# p2m-001.net
KiCad netlist of a schematic drawn in EAGLE
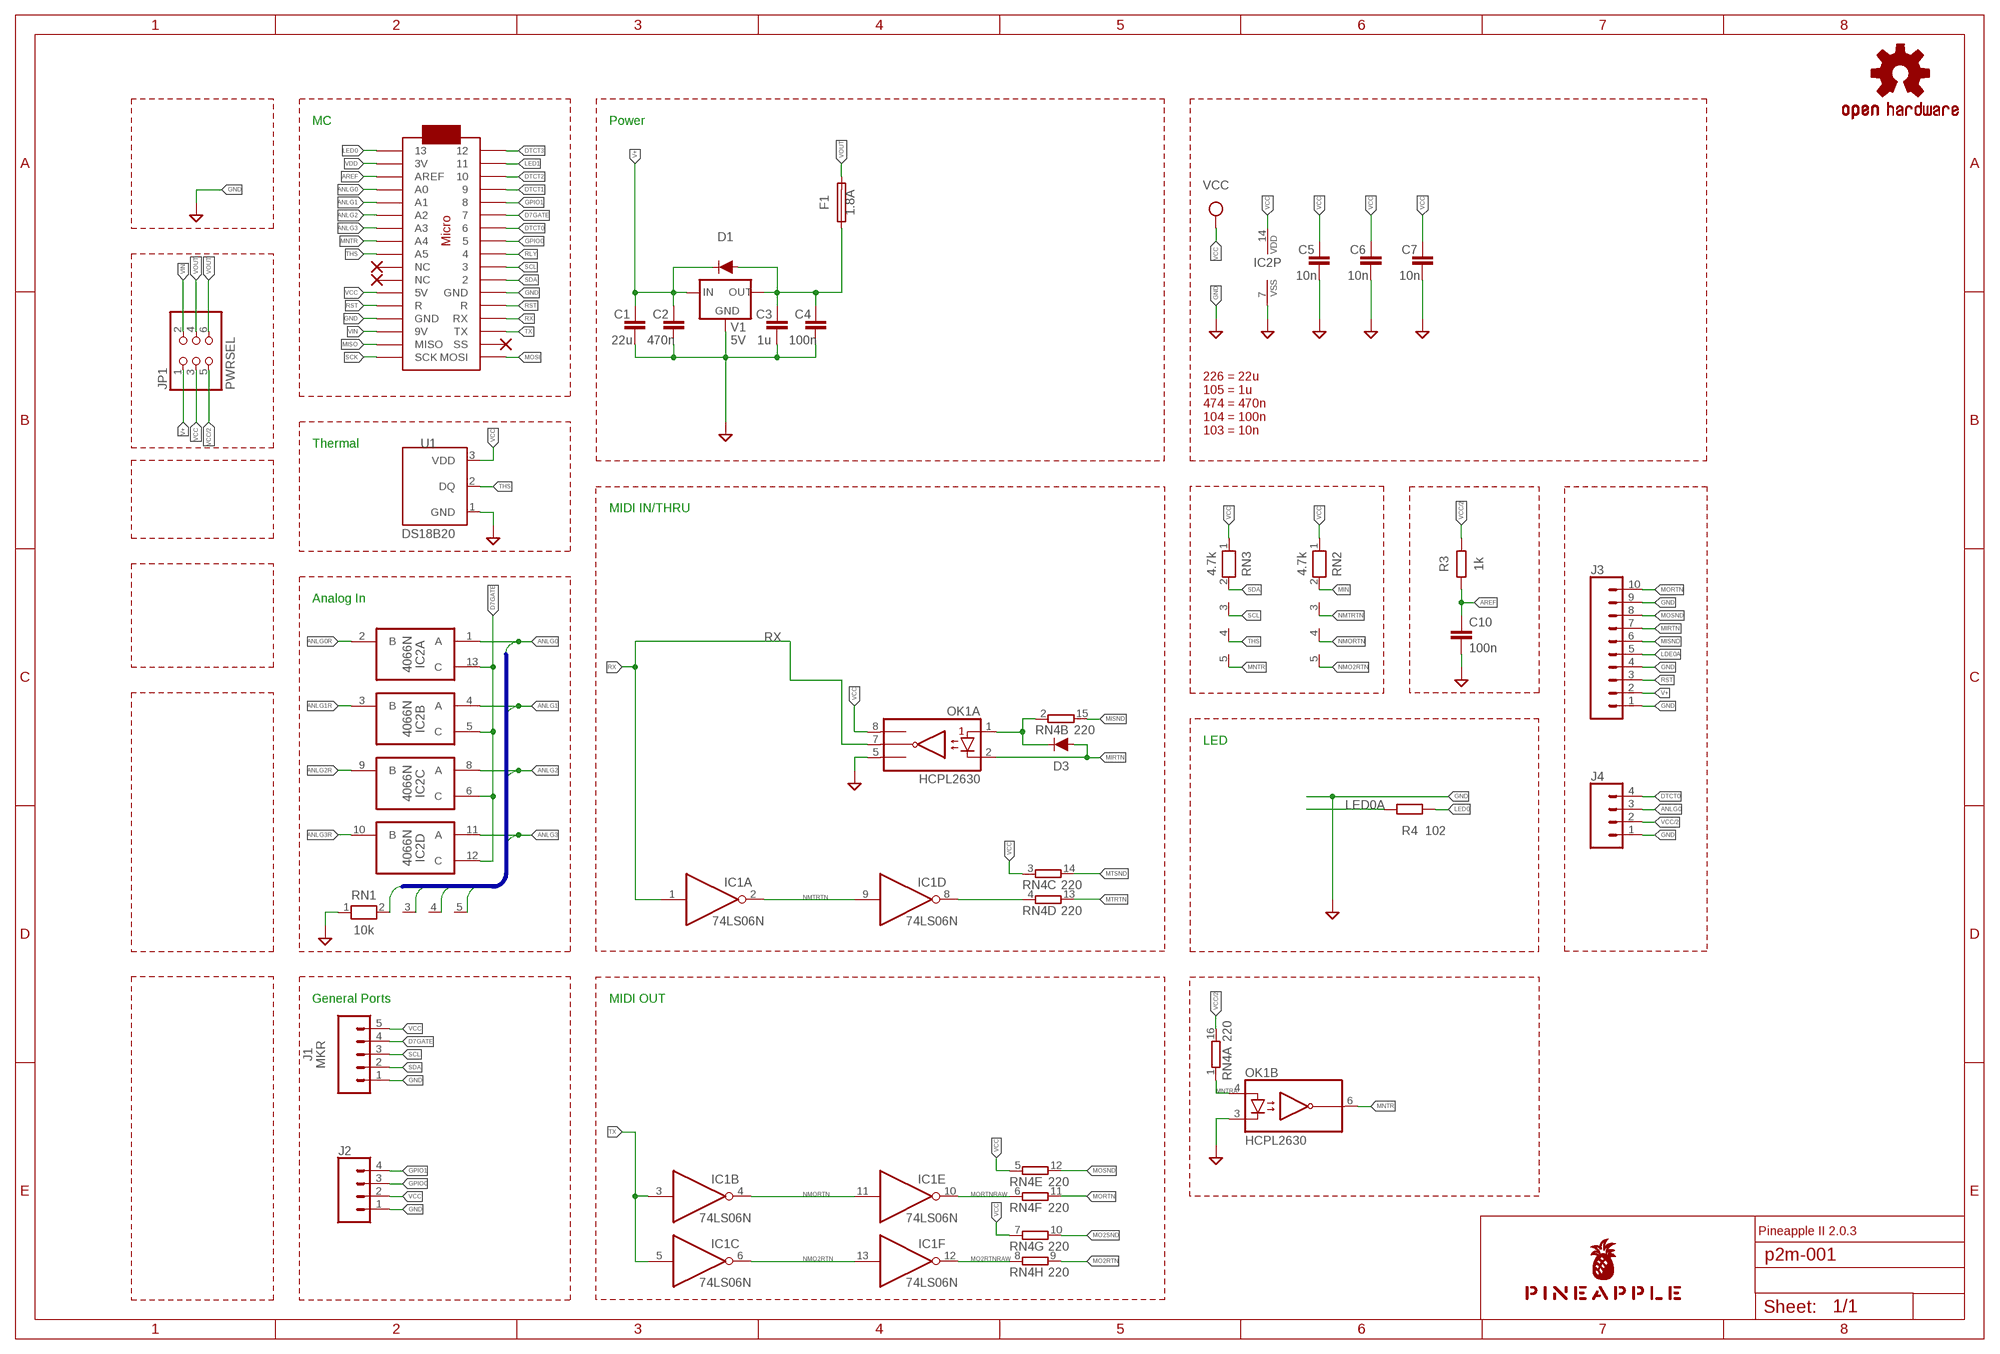
[diagram p0: schematic, sheet 1]

(export (version "E")
  (design (tool "Eeschema 10.0.6"))
  (components
    (comp (ref "C1")
      (value "22u")
      (footprint "eagle-import:C025-050X050")
      (libsource (lib "eagle-import") (part "C-EU025-050X050"))
    )
    (comp (ref "C2")
      (value "470n")
      (footprint "eagle-import:C050-024X044")
      (libsource (lib "eagle-import") (part "C-EU050-024X044"))
    )
    (comp (ref "C3")
      (value "1u")
      (footprint "eagle-import:C050-024X044")
      (libsource (lib "eagle-import") (part "C-EU050-024X044"))
    )
    (comp (ref "C4")
      (value "100n")
      (footprint "eagle-import:C025-024X044")
      (libsource (lib "eagle-import") (part "C-EU025-024X044"))
    )
    (comp (ref "C5")
      (value "10n")
      (footprint "eagle-import:C025-024X044")
      (libsource (lib "eagle-import") (part "resistor_348_C-EU025-024X044"))
    )
    (comp (ref "C6")
      (value "10n")
      (footprint "eagle-import:C025-024X044")
      (libsource (lib "eagle-import") (part "resistor_348_C-EU025-024X044"))
    )
    (comp (ref "C7")
      (value "10n")
      (footprint "eagle-import:C025-024X044")
      (libsource (lib "eagle-import") (part "resistor_348_C-EU025-024X044"))
    )
    (comp (ref "C10")
      (value "100n")
      (footprint "eagle-import:C025-024X044")
      (libsource (lib "eagle-import") (part "C-EU025-024X044"))
    )
    (comp (ref "D1")
      (value "DIODE-1N4148")
      (footprint "eagle-import:DIODE-1N4148")
      (libsource (lib "eagle-import") (part "DIODE-1N4148"))
    )
    (comp (ref "D3")
      (value "DIODE-1N4148")
      (footprint "eagle-import:DIODE-1N4148")
      (libsource (lib "eagle-import") (part "DIODE-1N4148"))
    )
    (comp (ref "F1")
      (value "1.8A")
      (footprint "eagle-import:TE5")
      (libsource (lib "eagle-import") (part "TE5"))
    )
    (comp (ref "IC1")
      (value "74LS06N")
      (footprint "eagle-import:DIL14")
      (libsource (lib "eagle-import") (part "7406NLS"))
    )
    (comp (ref "IC2")
      (value "4066N")
      (footprint "eagle-import:DIL14")
      (libsource (lib "eagle-import") (part "4066N"))
    )
    (comp (ref "J1")
      (value "MKR")
      (footprint "eagle-import:JST-5-PTH")
      (libsource (lib "eagle-import") (part "CONN_05JST"))
    )
    (comp (ref "J2")
      (value "CONN_04JST-PTH")
      (footprint "eagle-import:JST-4-PTH")
      (libsource (lib "eagle-import") (part "CONN_04JST-PTH"))
    )
    (comp (ref "J3")
      (value "CONN_102MM")
      (footprint "eagle-import:1X10-2MM")
      (libsource (lib "eagle-import") (part "CONN_102MM"))
    )
    (comp (ref "J4")
      (value "CONN_04JST-PTH")
      (footprint "eagle-import:JST-4-PTH")
      (libsource (lib "eagle-import") (part "CONN_04JST-PTH"))
    )
    (comp (ref "JP1")
      (value "PWRSEL")
      (footprint "eagle-import:2X03")
      (libsource (lib "eagle-import") (part "PINHD-2X3"))
    )
    (comp (ref "LOGO1")
      (value "OSHW-LOGOS-COPPER")
      (footprint "eagle-import:OSHW-LOGO-S_COPPER")
      (libsource (lib "eagle-import") (part "OSHW-LOGOS-COPPER"))
    )
    (comp (ref "MC1")
      (value "ARDUINOMICRO")
      (footprint "eagle-import:ARDUINOMICRO")
      (libsource (lib "eagle-import") (part "ARDUINOMICRO"))
    )
    (comp (ref "OK1")
      (value "HCPL2630")
      (footprint "eagle-import:DIL08")
      (fields (field (name "MF") "AGILENT TECHNOLOGIES") (field (name "MPN") "HCPL-2630-000E"))
      (libsource (lib "eagle-import") (part "HCPL2630"))
    )
    (comp (ref "R3")
      (value "1k")
      (footprint "eagle-import:0204_5")
      (libsource (lib "eagle-import") (part "R-EU_0204/5"))
    )
    (comp (ref "R4")
      (value "102")
      (footprint "eagle-import:0204_5")
      (libsource (lib "eagle-import") (part "R-EU_0204/5"))
    )
    (comp (ref "RN1")
      (value "10k")
      (footprint "eagle-import:RN-5")
      (libsource (lib "eagle-import") (part "RN04"))
    )
    (comp (ref "RN2")
      (value "4.7k")
      (footprint "eagle-import:RN-5")
      (libsource (lib "eagle-import") (part "RN04"))
    )
    (comp (ref "RN3")
      (value "4.7k")
      (footprint "eagle-import:RN-5")
      (libsource (lib "eagle-import") (part "RN04"))
    )
    (comp (ref "RN4")
      (value "220")
      (footprint "eagle-import:DIL16")
      (libsource (lib "eagle-import") (part "8R-N"))
    )
    (comp (ref "U$1")
      (value "PINEAPPLE450_SILK")
      (footprint "eagle-import:PINEAPPLE450_SILK")
      (libsource (lib "eagle-import") (part "PINEAPPLE450_SILK"))
    )
    (comp (ref "U1")
      (value "DS18B20")
      (footprint "eagle-import:TO-92-AMMO")
      (libsource (lib "eagle-import") (part "DS18B20"))
    )
    (comp (ref "V1")
      (value "5V")
      (footprint "eagle-import:78XXL")
      (libsource (lib "eagle-import") (part "78XXL"))
    )
  )
  (nets
    (net (code "1") (name "/LED0A") (class "Default")
      (node (ref "R4") (pin "1") (pinfunction "1_1") (pintype "passive"))
    )
    (net (code "2") (name "/MNTRA") (class "Default")
      (node (ref "OK1") (pin "4") (pinfunction "A2_4") (pintype "passive"))
      (node (ref "RN4") (pin "1") (pinfunction "1_1") (pintype "passive"))
    )
    (net (code "3") (name "/MO2RTNRAW") (class "Default")
      (node (ref "IC1") (pin "12") (pinfunction "O_12") (pintype "open_collector"))
      (node (ref "RN4") (pin "8") (pinfunction "1_8") (pintype "passive"))
    )
    (net (code "4") (name "/MORTNRAW") (class "Default")
      (node (ref "IC1") (pin "10") (pinfunction "O_10") (pintype "open_collector"))
      (node (ref "RN4") (pin "6") (pinfunction "1_6") (pintype "passive"))
    )
    (net (code "5") (name "ANLG0") (class "Default")
      (node (ref "IC2") (pin "1") (pinfunction "A_1") (pintype "tri_state"))
      (node (ref "J4") (pin "3") (pinfunction "3_3") (pintype "passive"))
      (node (ref "MC1") (pin "P$31") (pinfunction "A0_P$31") (pintype "bidirectional"))
      (node (ref "RN1") (pin "2") (pinfunction "2_2") (pintype "passive"))
    )
    (net (code "6") (name "ANLG0R") (class "Default")
      (node (ref "IC2") (pin "2") (pinfunction "B_2") (pintype "tri_state"))
    )
    (net (code "7") (name "ANLG1") (class "Default")
      (node (ref "IC2") (pin "4") (pinfunction "A_4") (pintype "tri_state"))
      (node (ref "MC1") (pin "P$30") (pinfunction "A1_P$30") (pintype "bidirectional"))
      (node (ref "RN1") (pin "3") (pinfunction "3_3") (pintype "passive"))
    )
    (net (code "8") (name "ANLG1R") (class "Default")
      (node (ref "IC2") (pin "3") (pinfunction "B_3") (pintype "tri_state"))
    )
    (net (code "9") (name "ANLG2") (class "Default")
      (node (ref "IC2") (pin "8") (pinfunction "A_8") (pintype "tri_state"))
      (node (ref "MC1") (pin "P$29") (pinfunction "A2_P$29") (pintype "bidirectional"))
      (node (ref "RN1") (pin "4") (pinfunction "4_4") (pintype "passive"))
    )
    (net (code "10") (name "ANLG2R") (class "Default")
      (node (ref "IC2") (pin "9") (pinfunction "B_9") (pintype "tri_state"))
    )
    (net (code "11") (name "ANLG3") (class "Default")
      (node (ref "IC2") (pin "11") (pinfunction "A_11") (pintype "tri_state"))
      (node (ref "MC1") (pin "P$28") (pinfunction "A3_P$28") (pintype "bidirectional"))
      (node (ref "RN1") (pin "5") (pinfunction "5_5") (pintype "passive"))
    )
    (net (code "12") (name "ANLG3R") (class "Default")
      (node (ref "IC2") (pin "10") (pinfunction "B_10") (pintype "tri_state"))
    )
    (net (code "13") (name "AREF") (class "Default")
      (node (ref "C10") (pin "1") (pinfunction "1_1") (pintype "passive"))
      (node (ref "MC1") (pin "P$32") (pinfunction "AREF_P$32") (pintype "bidirectional"))
      (node (ref "R3") (pin "1") (pinfunction "1_1") (pintype "passive"))
    )
    (net (code "14") (name "D7GATE") (class "Default")
      (node (ref "IC2") (pin "12") (pinfunction "C_12") (pintype "input"))
      (node (ref "IC2") (pin "13") (pinfunction "C_13") (pintype "input"))
      (node (ref "IC2") (pin "5") (pinfunction "C_5") (pintype "input"))
      (node (ref "IC2") (pin "6") (pinfunction "C_6") (pintype "input"))
      (node (ref "J1") (pin "4") (pinfunction "4_4") (pintype "passive"))
      (node (ref "MC1") (pin "P$6") (pinfunction "7_P$6") (pintype "bidirectional"))
    )
    (net (code "15") (name "DTCT0") (class "Default")
      (node (ref "J4") (pin "4") (pinfunction "4_4") (pintype "passive"))
      (node (ref "MC1") (pin "P$7") (pinfunction "6_P$7") (pintype "bidirectional"))
    )
    (net (code "16") (name "DTCT1") (class "Default")
      (node (ref "MC1") (pin "P$4") (pinfunction "9_P$4") (pintype "bidirectional"))
    )
    (net (code "17") (name "DTCT2") (class "Default")
      (node (ref "MC1") (pin "P$3") (pinfunction "10_P$3") (pintype "bidirectional"))
    )
    (net (code "18") (name "DTCT3") (class "Default")
      (node (ref "MC1") (pin "P$1") (pinfunction "12_P$1") (pintype "bidirectional"))
    )
    (net (code "19") (name "GND") (class "Default")
      (node (ref "C1") (pin "2") (pinfunction "2_2") (pintype "passive"))
      (node (ref "C10") (pin "2") (pinfunction "2_2") (pintype "passive"))
      (node (ref "C2") (pin "2") (pinfunction "2_2") (pintype "passive"))
      (node (ref "C3") (pin "2") (pinfunction "2_2") (pintype "passive"))
      (node (ref "C4") (pin "2") (pinfunction "2_2") (pintype "passive"))
      (node (ref "C5") (pin "2") (pinfunction "2_2") (pintype "passive"))
      (node (ref "C6") (pin "2") (pinfunction "2_2") (pintype "passive"))
      (node (ref "C7") (pin "2") (pinfunction "2_2") (pintype "passive"))
      (node (ref "IC2") (pin "7") (pinfunction "VSS_7") (pintype "power_in"))
      (node (ref "J1") (pin "1") (pinfunction "1_1") (pintype "passive"))
      (node (ref "J2") (pin "1") (pinfunction "1_1") (pintype "passive"))
      (node (ref "J3") (pin "1") (pinfunction "1_1") (pintype "passive"))
      (node (ref "J3") (pin "4") (pinfunction "4_4") (pintype "passive"))
      (node (ref "J3") (pin "9") (pinfunction "9_9") (pintype "passive"))
      (node (ref "J4") (pin "1") (pinfunction "1_1") (pintype "passive"))
      (node (ref "MC1") (pin "P$12") (pinfunction "GND_P$12") (pintype "bidirectional"))
      (node (ref "MC1") (pin "P$21") (pinfunction "GND_P$21") (pintype "bidirectional"))
      (node (ref "OK1") (pin "3") (pinfunction "C2_3") (pintype "passive"))
      (node (ref "OK1") (pin "5") (pinfunction "GND_5") (pintype "passive"))
      (node (ref "RN1") (pin "1") (pinfunction "1_1") (pintype "passive"))
      (node (ref "U1") (pin "1") (pinfunction "GND_1") (pintype "power_in"))
      (node (ref "V1") (pin "GND") (pinfunction "GND_GND") (pintype "input"))
    )
    (net (code "20") (name "GPIO0") (class "Default")
      (node (ref "J2") (pin "3") (pinfunction "3_3") (pintype "passive"))
      (node (ref "MC1") (pin "P$8") (pinfunction "5_P$8") (pintype "bidirectional"))
    )
    (net (code "21") (name "GPIO1") (class "Default")
      (node (ref "J2") (pin "4") (pinfunction "4_4") (pintype "passive"))
      (node (ref "MC1") (pin "P$5") (pinfunction "8_P$5") (pintype "bidirectional"))
    )
    (net (code "22") (name "LDE0A") (class "Default")
      (node (ref "J3") (pin "5") (pinfunction "5_5") (pintype "passive"))
    )
    (net (code "23") (name "LED0") (class "Default")
      (node (ref "MC1") (pin "P$34") (pinfunction "13_P$34") (pintype "bidirectional"))
      (node (ref "R4") (pin "2") (pinfunction "2_2") (pintype "passive"))
    )
    (net (code "24") (name "LED1") (class "Default")
      (node (ref "MC1") (pin "P$2") (pinfunction "11_P$2") (pintype "bidirectional"))
    )
    (net (code "25") (name "MIN") (class "Default")
      (node (ref "RN2") (pin "2") (pinfunction "2_2") (pintype "passive"))
    )
    (net (code "26") (name "MIRTN") (class "Default")
      (node (ref "D3") (pin "A") (pinfunction "A_A") (pintype "passive"))
      (node (ref "J3") (pin "7") (pinfunction "7_7") (pintype "passive"))
      (node (ref "OK1") (pin "2") (pinfunction "C1_2") (pintype "passive"))
    )
    (net (code "27") (name "MISND") (class "Default")
      (node (ref "J3") (pin "6") (pinfunction "6_6") (pintype "passive"))
      (node (ref "RN4") (pin "15") (pinfunction "2_15") (pintype "passive"))
    )
    (net (code "28") (name "MISO") (class "Default")
      (node (ref "MC1") (pin "P$19") (pinfunction "MISO_P$19") (pintype "bidirectional"))
    )
    (net (code "29") (name "MNTR") (class "Default")
      (node (ref "MC1") (pin "P$27") (pinfunction "A4_P$27") (pintype "bidirectional"))
      (node (ref "OK1") (pin "6") (pinfunction "VO2_6") (pintype "passive"))
      (node (ref "RN3") (pin "5") (pinfunction "5_5") (pintype "passive"))
    )
    (net (code "30") (name "MO2RTN") (class "Default")
      (node (ref "RN4") (pin "9") (pinfunction "2_9") (pintype "passive"))
    )
    (net (code "31") (name "MO2SND") (class "Default")
      (node (ref "RN4") (pin "10") (pinfunction "2_10") (pintype "passive"))
    )
    (net (code "32") (name "MORTN") (class "Default")
      (node (ref "J3") (pin "10") (pinfunction "10_10") (pintype "passive"))
      (node (ref "RN4") (pin "11") (pinfunction "2_11") (pintype "passive"))
    )
    (net (code "33") (name "MOSI") (class "Default")
      (node (ref "MC1") (pin "P$17") (pinfunction "MOSI_P$17") (pintype "bidirectional"))
    )
    (net (code "34") (name "MOSND") (class "Default")
      (node (ref "J3") (pin "8") (pinfunction "8_8") (pintype "passive"))
      (node (ref "RN4") (pin "12") (pinfunction "2_12") (pintype "passive"))
    )
    (net (code "35") (name "MTRTN") (class "Default")
      (node (ref "RN4") (pin "13") (pinfunction "2_13") (pintype "passive"))
    )
    (net (code "36") (name "MTSND") (class "Default")
      (node (ref "RN4") (pin "14") (pinfunction "2_14") (pintype "passive"))
    )
    (net (code "37") (name "NMO2RTN") (class "Default")
      (node (ref "IC1") (pin "13") (pinfunction "I_13") (pintype "input"))
      (node (ref "IC1") (pin "6") (pinfunction "O_6") (pintype "open_collector"))
      (node (ref "RN2") (pin "5") (pinfunction "5_5") (pintype "passive"))
    )
    (net (code "38") (name "NMORTN") (class "Default")
      (node (ref "IC1") (pin "11") (pinfunction "I_11") (pintype "input"))
      (node (ref "IC1") (pin "4") (pinfunction "O_4") (pintype "open_collector"))
      (node (ref "RN2") (pin "4") (pinfunction "4_4") (pintype "passive"))
    )
    (net (code "39") (name "NMTRTN") (class "Default")
      (node (ref "IC1") (pin "2") (pinfunction "O_2") (pintype "open_collector"))
      (node (ref "IC1") (pin "9") (pinfunction "I_9") (pintype "input"))
      (node (ref "RN2") (pin "3") (pinfunction "3_3") (pintype "passive"))
    )
    (net (code "40") (name "Net-(C3-Pad1)") (class "Default")
      (node (ref "C3") (pin "1") (pinfunction "1_1") (pintype "passive"))
      (node (ref "C4") (pin "1") (pinfunction "1_1") (pintype "passive"))
      (node (ref "D1") (pin "A") (pinfunction "A_A") (pintype "passive"))
      (node (ref "F1") (pin "1") (pinfunction "1_1") (pintype "passive"))
      (node (ref "V1") (pin "OUT") (pinfunction "OUT_OUT") (pintype "passive"))
    )
    (net (code "41") (name "Net-(IC1D-O)") (class "Default")
      (node (ref "IC1") (pin "8") (pinfunction "O_8") (pintype "open_collector"))
      (node (ref "RN4") (pin "4") (pinfunction "1_4") (pintype "passive"))
    )
    (net (code "42") (name "Net-(OK1A-A1)") (class "Default")
      (node (ref "D3") (pin "C") (pinfunction "C_C") (pintype "passive"))
      (node (ref "OK1") (pin "1") (pinfunction "A1_1") (pintype "passive"))
      (node (ref "RN4") (pin "2") (pinfunction "1_2") (pintype "passive"))
    )
    (net (code "43") (name "RLY") (class "Default")
      (node (ref "MC1") (pin "P$9") (pinfunction "4_P$9") (pintype "bidirectional"))
    )
    (net (code "44") (name "RST") (class "Default")
      (node (ref "J3") (pin "3") (pinfunction "3_3") (pintype "passive"))
      (node (ref "MC1") (pin "P$13") (pinfunction "R_P$13") (pintype "bidirectional"))
      (node (ref "MC1") (pin "P$22") (pinfunction "R_P$22") (pintype "bidirectional"))
    )
    (net (code "45") (name "RX") (class "Default")
      (node (ref "IC1") (pin "1") (pinfunction "I_1") (pintype "input"))
      (node (ref "MC1") (pin "P$14") (pinfunction "RX_P$14") (pintype "bidirectional"))
      (node (ref "OK1") (pin "7") (pinfunction "VO1_7") (pintype "passive"))
    )
    (net (code "46") (name "SCK") (class "Default")
      (node (ref "MC1") (pin "P$18") (pinfunction "SCK_P$18") (pintype "bidirectional"))
    )
    (net (code "47") (name "SCL") (class "Default")
      (node (ref "J1") (pin "3") (pinfunction "3_3") (pintype "passive"))
      (node (ref "MC1") (pin "P$10") (pinfunction "3_P$10") (pintype "bidirectional"))
      (node (ref "RN3") (pin "3") (pinfunction "3_3") (pintype "passive"))
    )
    (net (code "48") (name "SDA") (class "Default")
      (node (ref "J1") (pin "2") (pinfunction "2_2") (pintype "passive"))
      (node (ref "MC1") (pin "P$11") (pinfunction "2_P$11") (pintype "bidirectional"))
      (node (ref "RN3") (pin "2") (pinfunction "2_2") (pintype "passive"))
    )
    (net (code "49") (name "THS") (class "Default")
      (node (ref "MC1") (pin "P$26") (pinfunction "A5_P$26") (pintype "bidirectional"))
      (node (ref "RN3") (pin "4") (pinfunction "4_4") (pintype "passive"))
      (node (ref "U1") (pin "2") (pinfunction "DQ_2") (pintype "bidirectional"))
    )
    (net (code "50") (name "TX") (class "Default")
      (node (ref "IC1") (pin "3") (pinfunction "I_3") (pintype "input"))
      (node (ref "IC1") (pin "5") (pinfunction "I_5") (pintype "input"))
      (node (ref "MC1") (pin "P$15") (pinfunction "TX_P$15") (pintype "bidirectional"))
    )
    (net (code "51") (name "V+") (class "Default")
      (node (ref "C1") (pin "1") (pinfunction "1_1") (pintype "passive"))
      (node (ref "C2") (pin "1") (pinfunction "1_1") (pintype "passive"))
      (node (ref "D1") (pin "C") (pinfunction "C_C") (pintype "passive"))
      (node (ref "J3") (pin "2") (pinfunction "2_2") (pintype "passive"))
      (node (ref "JP1") (pin "1") (pinfunction "1_1") (pintype "passive"))
      (node (ref "V1") (pin "IN") (pinfunction "IN_IN") (pintype "input"))
    )
    (net (code "52") (name "VCC") (class "Default")
      (node (ref "C5") (pin "1") (pinfunction "1_1") (pintype "passive"))
      (node (ref "C6") (pin "1") (pinfunction "1_1") (pintype "passive"))
      (node (ref "C7") (pin "1") (pinfunction "1_1") (pintype "passive"))
      (node (ref "IC2") (pin "14") (pinfunction "VDD_14") (pintype "power_in"))
      (node (ref "J1") (pin "5") (pinfunction "5_5") (pintype "passive"))
      (node (ref "J2") (pin "2") (pinfunction "2_2") (pintype "passive"))
      (node (ref "JP1") (pin "3") (pinfunction "3_3") (pintype "passive"))
      (node (ref "MC1") (pin "P$23") (pinfunction "5V_P$23") (pintype "bidirectional"))
      (node (ref "OK1") (pin "8") (pinfunction "VCC_8") (pintype "passive"))
      (node (ref "RN2") (pin "1") (pinfunction "1_1") (pintype "passive"))
      (node (ref "RN3") (pin "1") (pinfunction "1_1") (pintype "passive"))
      (node (ref "RN4") (pin "3") (pinfunction "1_3") (pintype "passive"))
      (node (ref "RN4") (pin "5") (pinfunction "1_5") (pintype "passive"))
      (node (ref "RN4") (pin "7") (pinfunction "1_7") (pintype "passive"))
      (node (ref "U1") (pin "3") (pinfunction "VDD_3") (pintype "power_in"))
    )
    (net (code "53") (name "VCC{slash}2") (class "Default")
      (node (ref "J4") (pin "2") (pinfunction "2_2") (pintype "passive"))
      (node (ref "JP1") (pin "5") (pinfunction "5_5") (pintype "passive"))
      (node (ref "R3") (pin "2") (pinfunction "2_2") (pintype "passive"))
      (node (ref "RN4") (pin "16") (pinfunction "2_16") (pintype "passive"))
    )
    (net (code "54") (name "VDD") (class "Default")
      (node (ref "MC1") (pin "P$33") (pinfunction "3V_P$33") (pintype "bidirectional"))
    )
    (net (code "55") (name "VIN") (class "Default")
      (node (ref "JP1") (pin "2") (pinfunction "2_2") (pintype "passive"))
      (node (ref "MC1") (pin "P$20") (pinfunction "9V_P$20") (pintype "bidirectional"))
    )
    (net (code "56") (name "VOUT") (class "Default")
      (node (ref "F1") (pin "2") (pinfunction "2_2") (pintype "passive"))
      (node (ref "JP1") (pin "4") (pinfunction "4_4") (pintype "passive"))
      (node (ref "JP1") (pin "6") (pinfunction "6_6") (pintype "passive"))
    )
    (net (code "57") (name "unconnected-(MC1-NC-PadP$24)") (class "Default")
      (node (ref "MC1") (pin "P$24") (pinfunction "NC_P$24") (pintype "bidirectional"))
    )
    (net (code "58") (name "unconnected-(MC1-NC-PadP$25)") (class "Default")
      (node (ref "MC1") (pin "P$25") (pinfunction "NC_P$25") (pintype "bidirectional"))
    )
    (net (code "59") (name "unconnected-(MC1-SS-PadP$16)") (class "Default")
      (node (ref "MC1") (pin "P$16") (pinfunction "SS_P$16") (pintype "bidirectional"))
    )
  )
)
